# LCDDisplay.net
KiCad netlist of a schematic drawn in Altium Designer
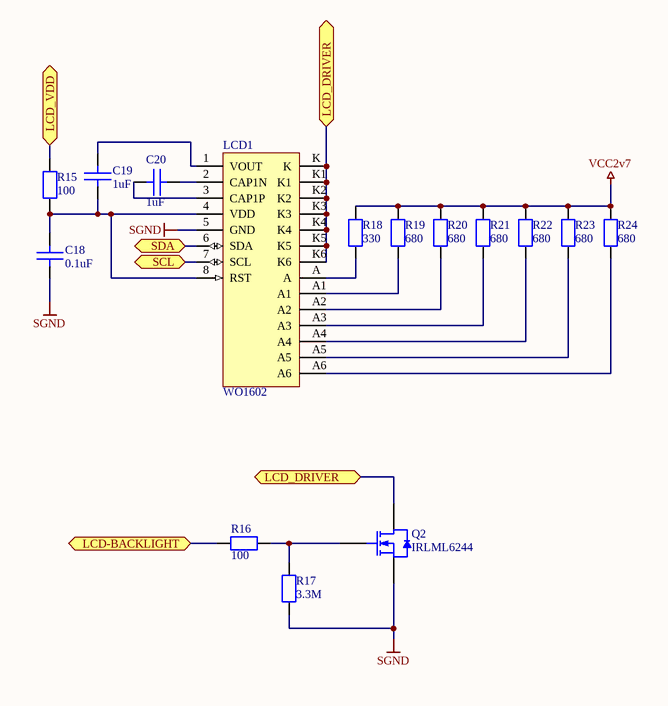
[diagram p0: LCDDisplay.SchDoc]

(export (version "E")
  (design (tool "Eeschema 10.0.6"))
  (components
    (comp (ref "C18")
      (value "0.1uF")
      (footprint "C0805")
      (description "C0.1uF-50V")
      (fields (field (name "VOLTAGE") "50V"))
      (libsource (lib "MCounter_Common") (part "C0.1uF-50V"))
    )
    (comp (ref "C19")
      (value "1uF")
      (footprint "C0805")
      (description "C1uF-50V")
      (fields (field (name "VOLTAGE") "50V"))
      (libsource (lib "MCounter_Common") (part "C1uF-50V"))
    )
    (comp (ref "C20")
      (value "1uF")
      (footprint "C0805")
      (description "C1uF-50V")
      (fields (field (name "VOLTAGE") "50V"))
      (libsource (lib "MCounter_Common") (part "C1uF-50V"))
    )
    (comp (ref "LCD1")
      (value "WO1602")
      (footprint "WO1602I")
      (description "LCD COG display 16x02")
      (libsource (lib "Chips") (part "WO1602"))
    )
    (comp (ref "Q2")
      (value "IRLML6244")
      (footprint "SOT23_N")
      (description "N-Channel Power MOSFET")
      (libsource (lib "MCounter_Common") (part "IRLML6244"))
    )
    (comp (ref "R15")
      (value "100")
      (footprint "R0805")
      (description "R-100-5%")
      (fields (field (name "Comment") "R100-5%"))
      (libsource (lib "MCounter_Common") (part "R100-5%"))
    )
    (comp (ref "R16")
      (value "100")
      (footprint "R0805")
      (description "R-100-5%")
      (fields (field (name "Comment") "R100-5%"))
      (libsource (lib "") (part "R100-5%_1"))
    )
    (comp (ref "R17")
      (value "3.3M")
      (footprint "R0805")
      (description "R3.3M-5%")
      (libsource (lib "MCounter_Common") (part "R3.3M-5%"))
    )
    (comp (ref "R18")
      (value "330")
      (footprint "R1206")
      (description "R-330-5%")
      (fields (field (name "Comment") "R330-5%"))
      (libsource (lib "MCounter_Common") (part "R330-5%"))
    )
    (comp (ref "R19")
      (value "680")
      (footprint "R1206")
      (description "R-680-5%")
      (fields (field (name "Comment") "R680-5%"))
      (libsource (lib "MCounter_Common") (part "R680-5%"))
    )
    (comp (ref "R20")
      (value "680")
      (footprint "R1206")
      (description "R-680-5%")
      (fields (field (name "Comment") "R680-5%"))
      (libsource (lib "MCounter_Common") (part "R680-5%"))
    )
    (comp (ref "R21")
      (value "680")
      (footprint "R1206")
      (description "R-680-5%")
      (fields (field (name "Comment") "R680-5%"))
      (libsource (lib "MCounter_Common") (part "R680-5%"))
    )
    (comp (ref "R22")
      (value "680")
      (footprint "R1206")
      (description "R-680-5%")
      (fields (field (name "Comment") "R680-5%"))
      (libsource (lib "MCounter_Common") (part "R680-5%"))
    )
    (comp (ref "R23")
      (value "680")
      (footprint "R1206")
      (description "R-680-5%")
      (fields (field (name "Comment") "R680-5%"))
      (libsource (lib "") (part "R680-5%_1"))
    )
    (comp (ref "R24")
      (value "680")
      (footprint "R1206")
      (description "R-680-5%")
      (fields (field (name "Comment") "R680-5%"))
      (libsource (lib "MCounter_Common") (part "R680-5%"))
    )
  )
  (nets
    (net (code "1") (name "/LCD-BACKLIGHT") (class "Default")
      (node (ref "R16") (pin "1") (pinfunction "1_1") (pintype "passive"))
    )
    (net (code "2") (name "/LCD_DRIVER") (class "Default")
      (node (ref "LCD1") (pin "K") (pinfunction "K_K") (pintype "power_in"))
      (node (ref "LCD1") (pin "K1") (pinfunction "K1_K1") (pintype "power_in"))
      (node (ref "LCD1") (pin "K2") (pinfunction "K2_K2") (pintype "power_in"))
      (node (ref "LCD1") (pin "K3") (pinfunction "K3_K3") (pintype "power_in"))
      (node (ref "LCD1") (pin "K4") (pinfunction "K4_K4") (pintype "power_in"))
      (node (ref "LCD1") (pin "K5") (pinfunction "K5_K5") (pintype "power_in"))
      (node (ref "LCD1") (pin "K6") (pinfunction "K6_K6") (pintype "power_in"))
      (node (ref "Q2") (pin "3") (pinfunction "D_3") (pintype "passive"))
    )
    (net (code "3") (name "/LCD_VDD") (class "Default")
      (node (ref "R15") (pin "2") (pinfunction "2_2") (pintype "passive"))
    )
    (net (code "4") (name "/SCL") (class "Default")
      (node (ref "LCD1") (pin "7") (pinfunction "SCL_7") (pintype "bidirectional"))
    )
    (net (code "5") (name "/SDA") (class "Default")
      (node (ref "LCD1") (pin "6") (pinfunction "SDA_6") (pintype "bidirectional"))
    )
    (net (code "6") (name "Net-(LCD1-CAP1N)") (class "Default")
      (node (ref "C20") (pin "1") (pinfunction "1_1") (pintype "passive"))
      (node (ref "LCD1") (pin "2") (pinfunction "CAP1N_2") (pintype "power_in"))
    )
    (net (code "7") (name "Net-(LCD1-CAP1P)") (class "Default")
      (node (ref "C20") (pin "2") (pinfunction "2_2") (pintype "passive"))
      (node (ref "LCD1") (pin "3") (pinfunction "CAP1P_3") (pintype "power_in"))
    )
    (net (code "8") (name "Net-(LCD1-PadA)") (class "Default")
      (node (ref "LCD1") (pin "A") (pinfunction "A_A") (pintype "power_in"))
      (node (ref "R18") (pin "1") (pinfunction "1_1") (pintype "passive"))
    )
    (net (code "9") (name "Net-(LCD1-PadA1)") (class "Default")
      (node (ref "LCD1") (pin "A1") (pinfunction "A1_A1") (pintype "power_in"))
      (node (ref "R19") (pin "1") (pinfunction "1_1") (pintype "passive"))
    )
    (net (code "10") (name "Net-(LCD1-PadA2)") (class "Default")
      (node (ref "LCD1") (pin "A2") (pinfunction "A2_A2") (pintype "power_in"))
      (node (ref "R20") (pin "1") (pinfunction "1_1") (pintype "passive"))
    )
    (net (code "11") (name "Net-(LCD1-PadA3)") (class "Default")
      (node (ref "LCD1") (pin "A3") (pinfunction "A3_A3") (pintype "power_in"))
      (node (ref "R21") (pin "1") (pinfunction "1_1") (pintype "passive"))
    )
    (net (code "12") (name "Net-(LCD1-PadA4)") (class "Default")
      (node (ref "LCD1") (pin "A4") (pinfunction "A4_A4") (pintype "power_in"))
      (node (ref "R22") (pin "1") (pinfunction "1_1") (pintype "passive"))
    )
    (net (code "13") (name "Net-(LCD1-PadA5)") (class "Default")
      (node (ref "LCD1") (pin "A5") (pinfunction "A5_A5") (pintype "power_in"))
      (node (ref "R23") (pin "2") (pinfunction "2_2") (pintype "passive"))
    )
    (net (code "14") (name "Net-(LCD1-PadA6)") (class "Default")
      (node (ref "LCD1") (pin "A6") (pinfunction "A6_A6") (pintype "power_in"))
      (node (ref "R24") (pin "1") (pinfunction "1_1") (pintype "passive"))
    )
    (net (code "15") (name "Net-(LCD1-RST)") (class "Default")
      (node (ref "C18") (pin "2") (pinfunction "2_2") (pintype "passive"))
      (node (ref "C19") (pin "2") (pinfunction "2_2") (pintype "passive"))
      (node (ref "LCD1") (pin "4") (pinfunction "VDD_4") (pintype "power_in"))
      (node (ref "LCD1") (pin "8") (pinfunction "RST_8") (pintype "input"))
      (node (ref "R15") (pin "1") (pinfunction "1_1") (pintype "passive"))
    )
    (net (code "16") (name "Net-(LCD1-VOUT)") (class "Default")
      (node (ref "C19") (pin "1") (pinfunction "1_1") (pintype "passive"))
      (node (ref "LCD1") (pin "1") (pinfunction "VOUT_1") (pintype "power_in"))
    )
    (net (code "17") (name "Net-(Q2-G)") (class "Default")
      (node (ref "Q2") (pin "1") (pinfunction "G_1") (pintype "passive"))
      (node (ref "R16") (pin "2") (pinfunction "2_2") (pintype "passive"))
      (node (ref "R17") (pin "1") (pinfunction "1_1") (pintype "passive"))
    )
    (net (code "18") (name "SGND") (class "Default")
      (node (ref "C18") (pin "1") (pinfunction "1_1") (pintype "passive"))
      (node (ref "LCD1") (pin "5") (pinfunction "GND_5") (pintype "power_in"))
      (node (ref "Q2") (pin "2") (pinfunction "S_2") (pintype "passive"))
      (node (ref "R17") (pin "2") (pinfunction "2_2") (pintype "passive"))
    )
    (net (code "19") (name "VCC2v7") (class "Default")
      (node (ref "R18") (pin "2") (pinfunction "2_2") (pintype "passive"))
      (node (ref "R19") (pin "2") (pinfunction "2_2") (pintype "passive"))
      (node (ref "R20") (pin "2") (pinfunction "2_2") (pintype "passive"))
      (node (ref "R21") (pin "2") (pinfunction "2_2") (pintype "passive"))
      (node (ref "R22") (pin "2") (pinfunction "2_2") (pintype "passive"))
      (node (ref "R23") (pin "1") (pinfunction "1_1") (pintype "passive"))
      (node (ref "R24") (pin "2") (pinfunction "2_2") (pintype "passive"))
    )
  )
)
